# SparkFun_I2S_Audio_Breakout.net
KiCad netlist of a schematic drawn in EAGLE
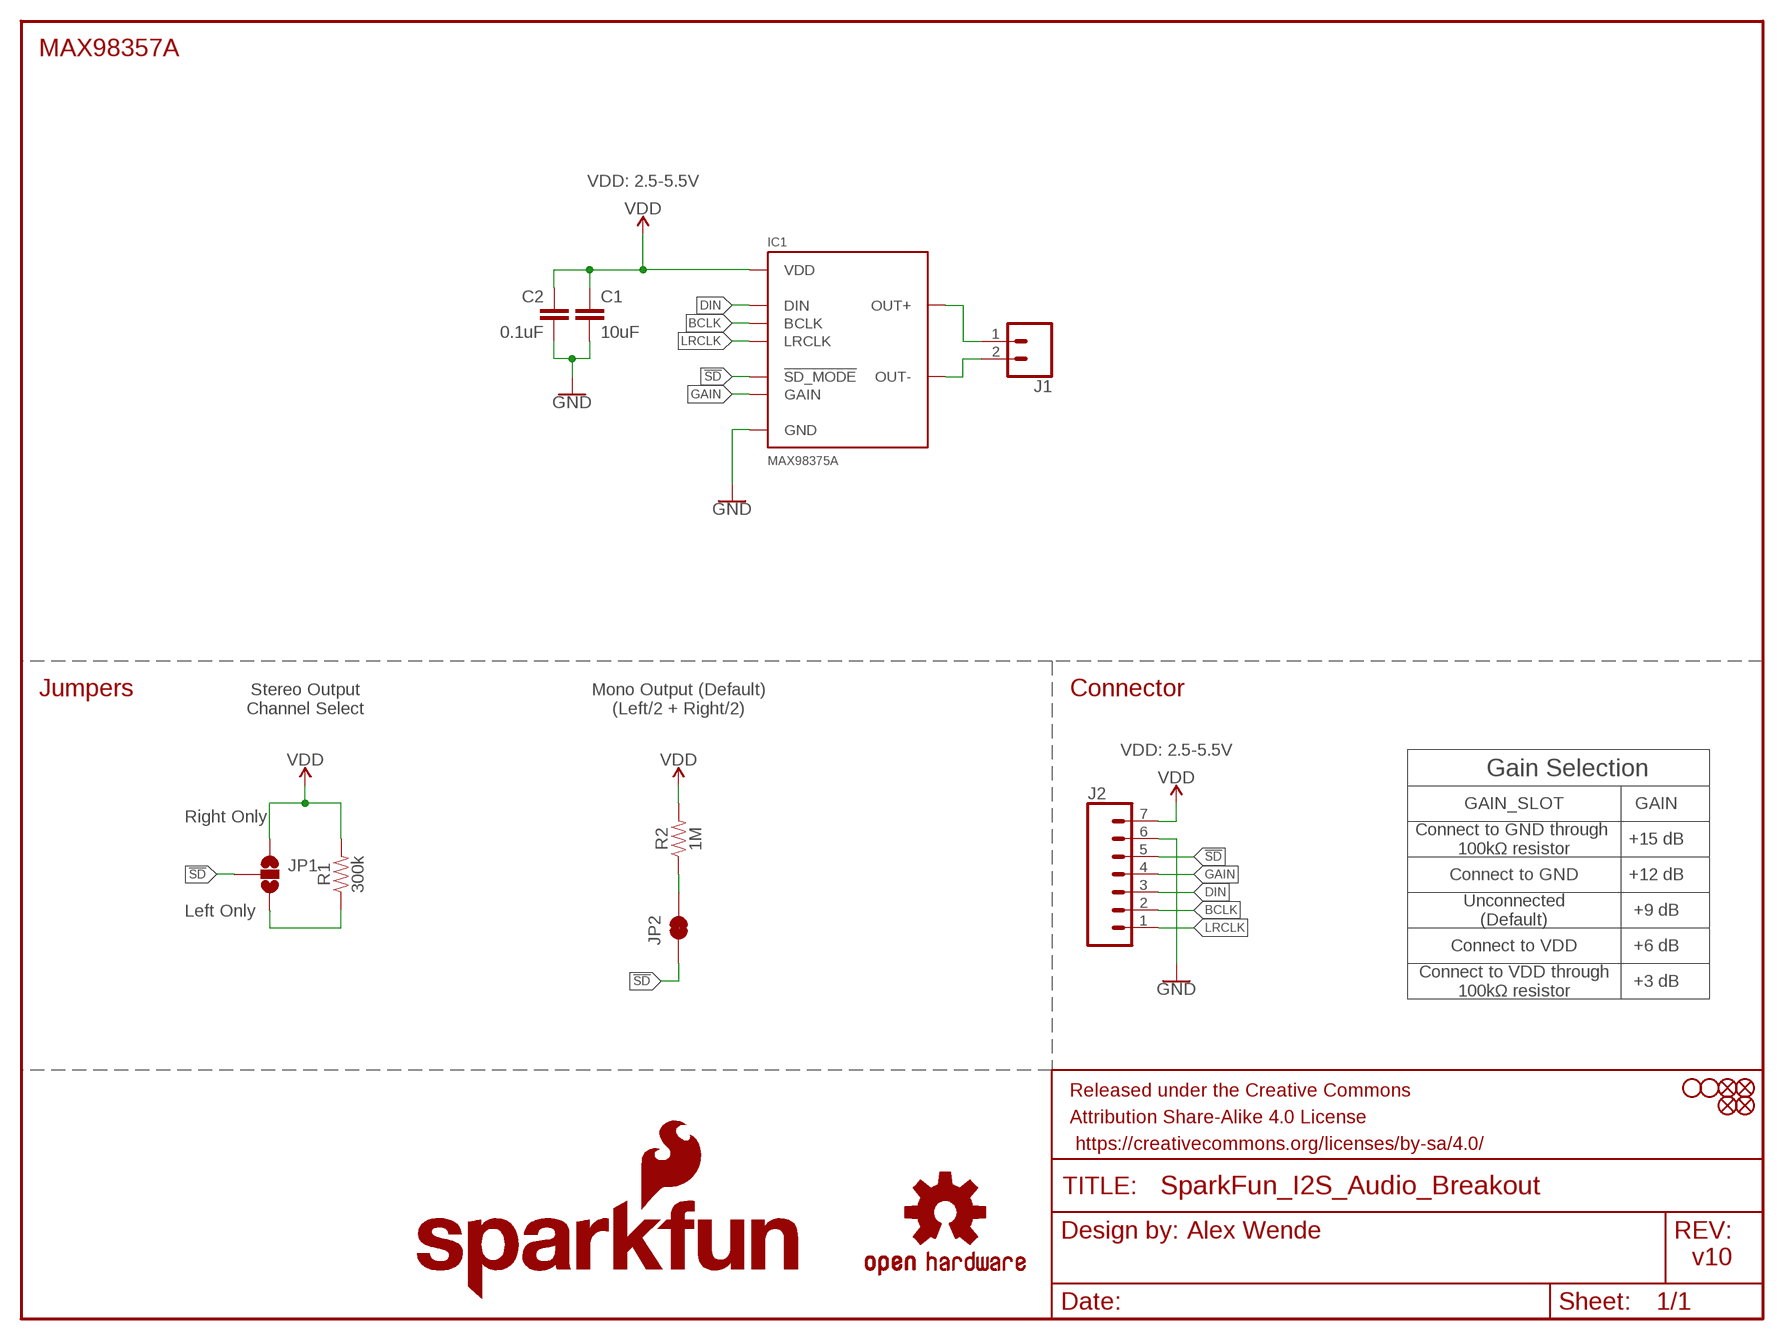
[diagram p0: schematic, sheet 1]

(export (version "E")
  (design (tool "Eeschema 10.0.6"))
  (components
    (comp (ref "C1")
      (value "10uF")
      (footprint "eagle-import:0805")
      (libsource (lib "eagle-import") (part "10UF-0805-10V-10%"))
    )
    (comp (ref "C2")
      (value "0.1uF")
      (footprint "eagle-import:0603")
      (libsource (lib "eagle-import") (part "0.1UF-0603-25V-(+80/-20%)"))
    )
    (comp (ref "FD1")
      (value "FIDUCIALUFIDUCIAL")
      (footprint "eagle-import:FIDUCIAL-MICRO")
      (libsource (lib "eagle-import") (part "FIDUCIALUFIDUCIAL"))
    )
    (comp (ref "FD2")
      (value "FIDUCIALUFIDUCIAL")
      (footprint "eagle-import:FIDUCIAL-MICRO")
      (libsource (lib "eagle-import") (part "FIDUCIALUFIDUCIAL"))
    )
    (comp (ref "FD3")
      (value "FIDUCIALUFIDUCIAL")
      (footprint "eagle-import:FIDUCIAL-MICRO")
      (libsource (lib "eagle-import") (part "FIDUCIALUFIDUCIAL"))
    )
    (comp (ref "FD4")
      (value "FIDUCIALUFIDUCIAL")
      (footprint "eagle-import:FIDUCIAL-MICRO")
      (libsource (lib "eagle-import") (part "FIDUCIALUFIDUCIAL"))
    )
    (comp (ref "FRAME1")
      (value "FRAME-LETTER")
      (footprint "eagle-import:CREATIVE_COMMONS")
      (libsource (lib "eagle-import") (part "FRAME-LETTER"))
    )
    (comp (ref "H1")
      (value "STAND-OFF")
      (footprint "eagle-import:STAND-OFF")
      (libsource (lib "eagle-import") (part "STAND-OFF"))
    )
    (comp (ref "H2")
      (value "STAND-OFF")
      (footprint "eagle-import:STAND-OFF")
      (libsource (lib "eagle-import") (part "STAND-OFF"))
    )
    (comp (ref "IC1")
      (value "MAX98375A")
      (footprint "eagle-import:TQFN-16")
      (libsource (lib "eagle-import") (part "MAX98357A"))
    )
    (comp (ref "J1")
      (value "CONN_023.5MM-NO_SILK")
      (footprint "eagle-import:SCREWTERMINAL-3.5MM-2-NS")
      (libsource (lib "eagle-import") (part "CONN_023.5MM-NO_SILK"))
    )
    (comp (ref "J2")
      (value "CONN_07NO_SILK")
      (footprint "eagle-import:1X07_NO_SILK")
      (libsource (lib "eagle-import") (part "CONN_07NO_SILK"))
    )
    (comp (ref "JP1")
      (value "JUMPER-SMT_3_NO_NO-SILK")
      (footprint "eagle-import:SMT-JUMPER_3_NO_NO-SILK")
      (libsource (lib "eagle-import") (part "JUMPER-SMT_3_NO_NO-SILK"))
    )
    (comp (ref "JP2")
      (value "JUMPER-SMT_2_NC_TRACE_NO-SILK")
      (footprint "eagle-import:SMT-JUMPER_2_NC_TRACE_NO-SILK")
      (libsource (lib "eagle-import") (part "JUMPER-SMT_2_NC_TRACE_NO-SILK"))
    )
    (comp (ref "LOGO1")
      (value "SFE_LOGO_NAME_FLAME.1_INCH")
      (footprint "eagle-import:SFE_LOGO_NAME_FLAME_.1")
      (libsource (lib "eagle-import") (part "SFE_LOGO_NAME_FLAME.1_INCH"))
    )
    (comp (ref "LOGO2")
      (value "OSHW-LOGOS")
      (footprint "eagle-import:OSHW-LOGO-S")
      (libsource (lib "eagle-import") (part "OSHW-LOGOS"))
    )
    (comp (ref "R1")
      (value "300k")
      (footprint "eagle-import:0603")
      (libsource (lib "eagle-import") (part "300KOHM-0603-1/10W-1%"))
    )
    (comp (ref "R2")
      (value "1M")
      (footprint "eagle-import:0603")
      (libsource (lib "eagle-import") (part "1MOHM-0603-1/4W-5%"))
    )
  )
  (nets
    (net (code "1") (name "/~{SD}") (class "Default")
      (node (ref "IC1") (pin "P$4") (pinfunction "~{SD_MODE}_P$4") (pintype "bidirectional"))
      (node (ref "J2") (pin "5") (pinfunction "5_5") (pintype "passive"))
      (node (ref "JP1") (pin "2") (pinfunction "2_2") (pintype "passive"))
      (node (ref "JP2") (pin "1") (pinfunction "1_1") (pintype "passive"))
    )
    (net (code "2") (name "BCLK") (class "Default")
      (node (ref "IC1") (pin "P$16") (pinfunction "BCLK_P$16") (pintype "bidirectional"))
      (node (ref "J2") (pin "2") (pinfunction "2_2") (pintype "passive"))
    )
    (net (code "3") (name "DIN") (class "Default")
      (node (ref "IC1") (pin "P$1") (pinfunction "DIN_P$1") (pintype "bidirectional"))
      (node (ref "J2") (pin "3") (pinfunction "3_3") (pintype "passive"))
    )
    (net (code "4") (name "GAIN") (class "Default")
      (node (ref "IC1") (pin "P$2") (pinfunction "GAIN_P$2") (pintype "bidirectional"))
      (node (ref "J2") (pin "4") (pinfunction "4_4") (pintype "passive"))
    )
    (net (code "5") (name "GND") (class "Default")
      (node (ref "C1") (pin "2") (pinfunction "2_2") (pintype "passive"))
      (node (ref "C2") (pin "2") (pinfunction "2_2") (pintype "passive"))
      (node (ref "IC1") (pin "P$11") (pinfunction "GND_P$11") (pintype "bidirectional"))
      (node (ref "IC1") (pin "P$15") (pinfunction "GND_P$15") (pintype "bidirectional"))
      (node (ref "IC1") (pin "P$3") (pinfunction "GND_P$3") (pintype "bidirectional"))
      (node (ref "IC1") (pin "P$EP") (pinfunction "GND_P$EP") (pintype "bidirectional"))
      (node (ref "J2") (pin "6") (pinfunction "6_6") (pintype "passive"))
    )
    (net (code "6") (name "LRCLK") (class "Default")
      (node (ref "IC1") (pin "P$14") (pinfunction "LRCLK_P$14") (pintype "bidirectional"))
      (node (ref "J2") (pin "1") (pinfunction "1_1") (pintype "passive"))
    )
    (net (code "7") (name "Net-(IC1-OUT+)") (class "Default")
      (node (ref "IC1") (pin "P$9") (pinfunction "OUT+_P$9") (pintype "bidirectional"))
      (node (ref "J1") (pin "1") (pinfunction "1_1") (pintype "passive"))
    )
    (net (code "8") (name "Net-(IC1-OUT-)") (class "Default")
      (node (ref "IC1") (pin "P$10") (pinfunction "OUT-_P$10") (pintype "bidirectional"))
      (node (ref "J1") (pin "2") (pinfunction "2_2") (pintype "passive"))
    )
    (net (code "9") (name "Net-(JP1-Pad3)") (class "Default")
      (node (ref "JP1") (pin "3") (pinfunction "3_3") (pintype "passive"))
      (node (ref "R1") (pin "1") (pinfunction "1_1") (pintype "passive"))
    )
    (net (code "10") (name "Net-(JP2-Pad2)") (class "Default")
      (node (ref "JP2") (pin "2") (pinfunction "2_2") (pintype "passive"))
      (node (ref "R2") (pin "1") (pinfunction "1_1") (pintype "passive"))
    )
    (net (code "11") (name "VDD") (class "Default")
      (node (ref "C1") (pin "1") (pinfunction "1_1") (pintype "passive"))
      (node (ref "C2") (pin "1") (pinfunction "1_1") (pintype "passive"))
      (node (ref "IC1") (pin "P$7") (pinfunction "VDD_P$7") (pintype "bidirectional"))
      (node (ref "IC1") (pin "P$8") (pinfunction "VDD_P$8") (pintype "bidirectional"))
      (node (ref "J2") (pin "7") (pinfunction "7_7") (pintype "passive"))
      (node (ref "JP1") (pin "1") (pinfunction "1_1") (pintype "passive"))
      (node (ref "R1") (pin "2") (pinfunction "2_2") (pintype "passive"))
      (node (ref "R2") (pin "2") (pinfunction "2_2") (pintype "passive"))
    )
  )
)
